# multiplier.net
KiCad netlist of a schematic drawn in Altium Designer
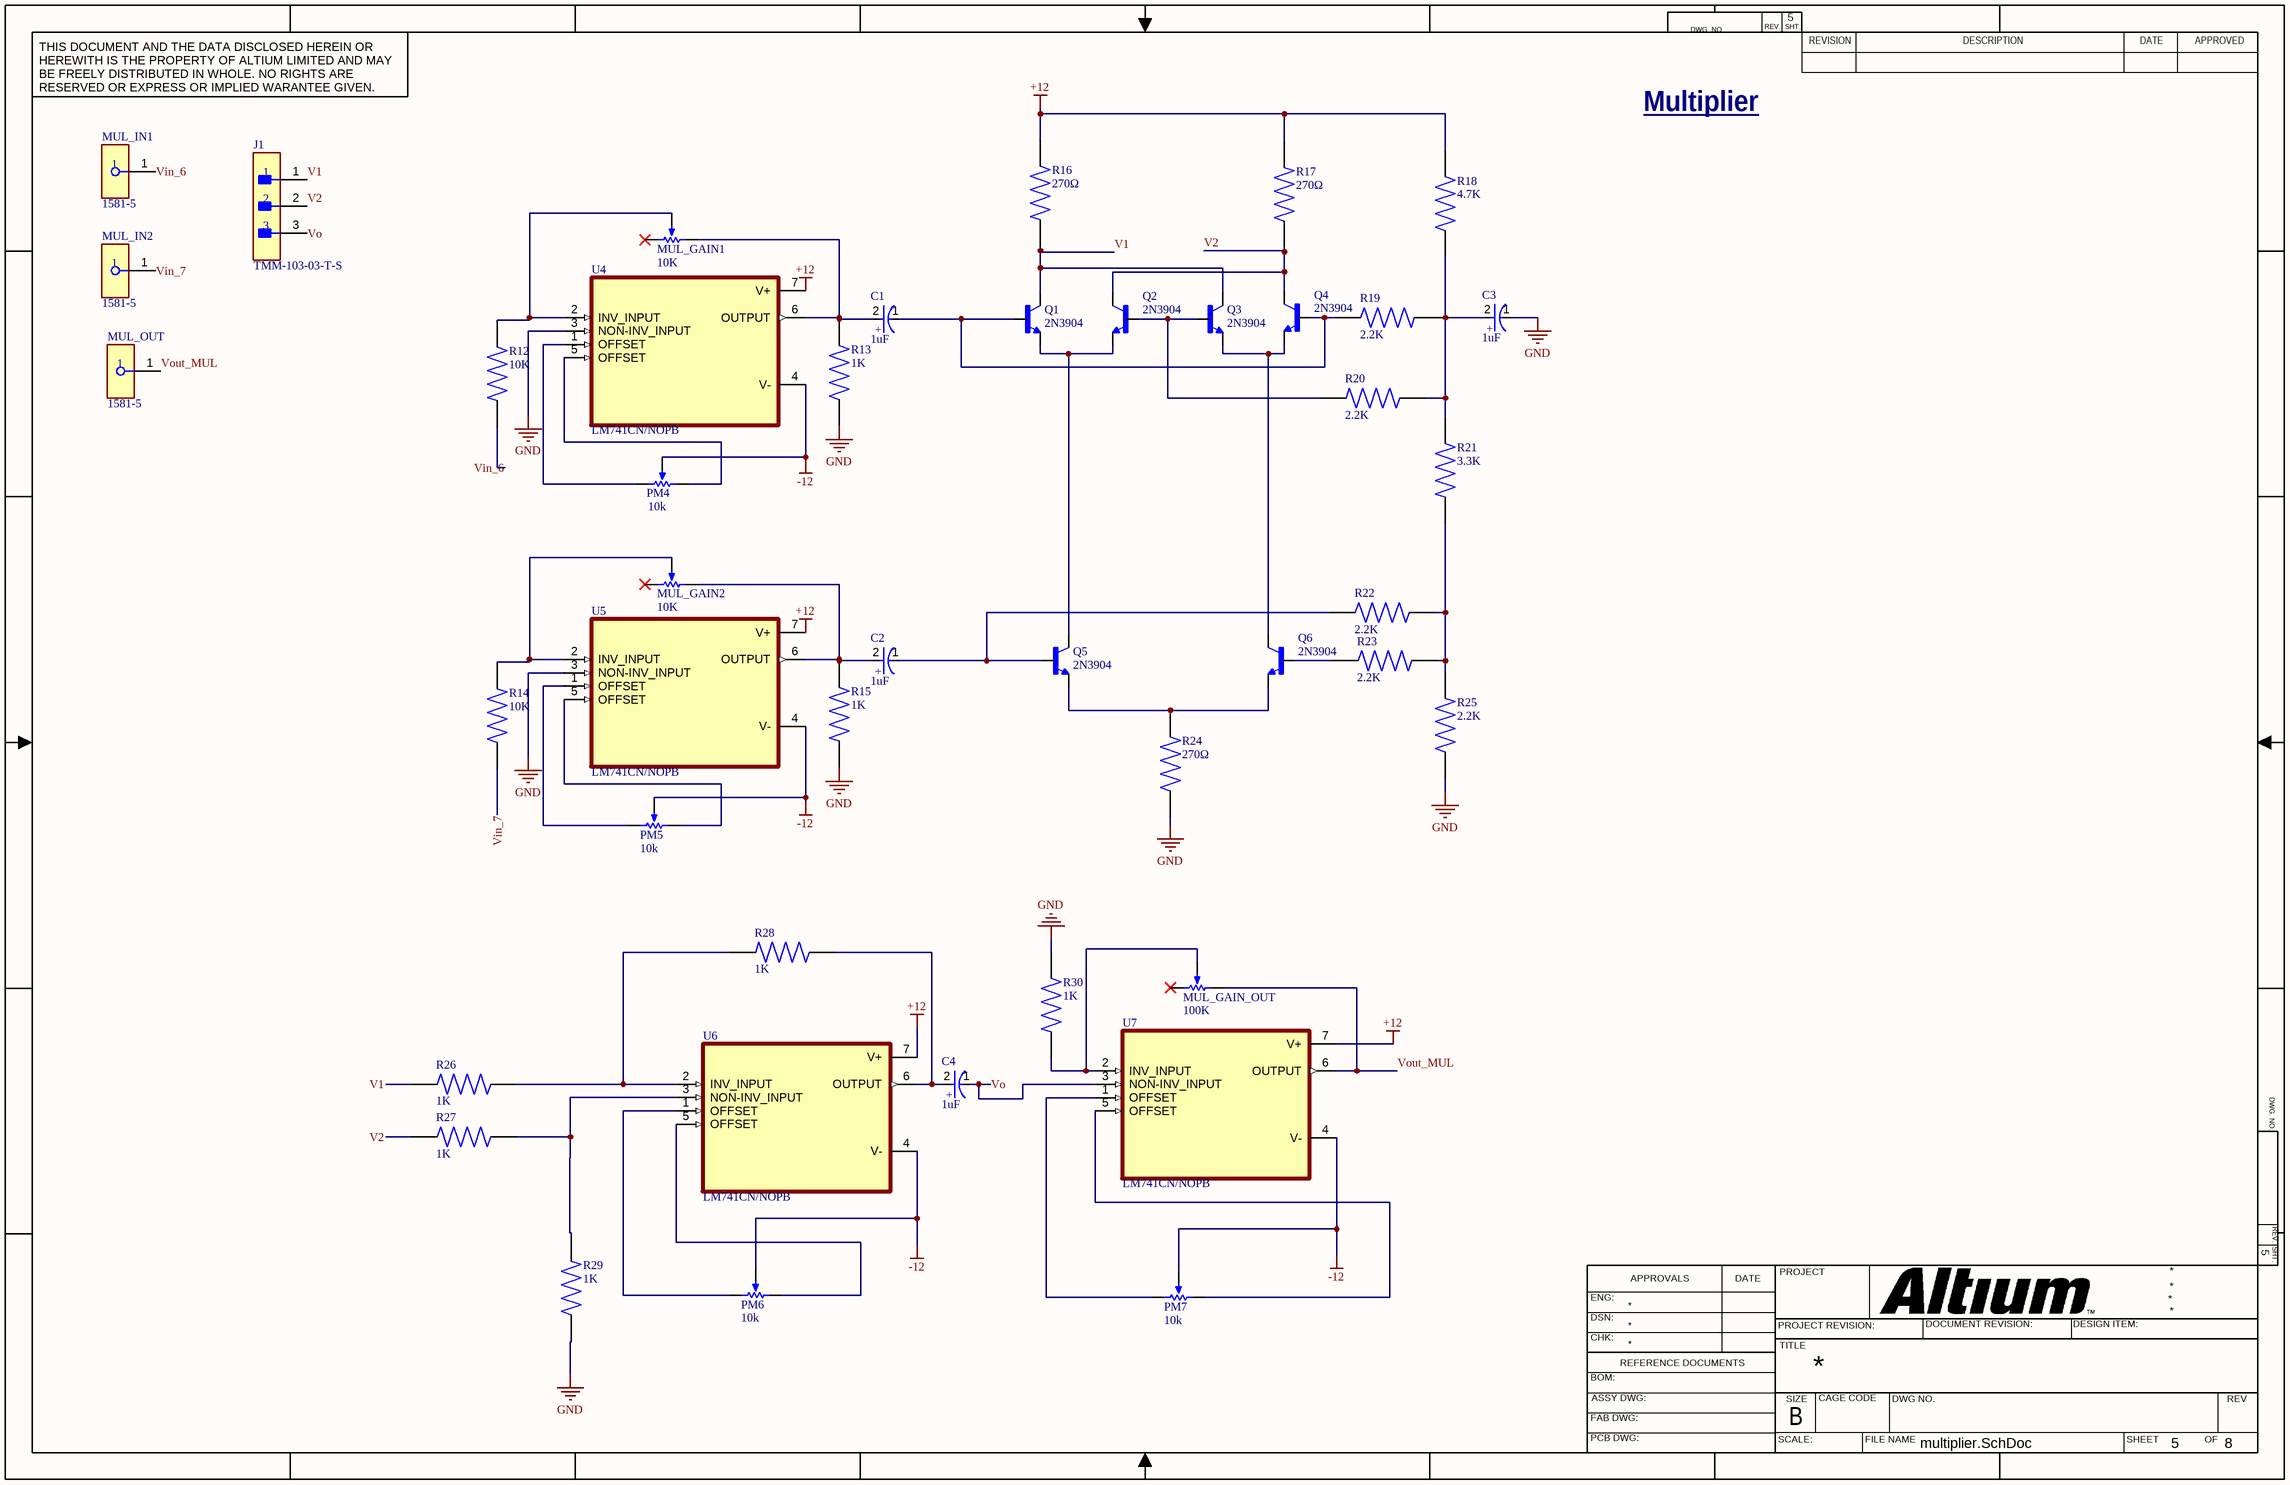
[diagram p0: multiplier.SchDoc]

(export (version "E")
  (design (tool "Eeschema 10.0.6"))
  (components
    (comp (ref "C1")
      (value "1uF")
      (footprint "FP-ECA-2CHG010I-MFG")
      (description "CAP ALUM 1UF 20% 160V RADIAL")
      (fields (field (name "TOLERANCE") "20%"))
      (libsource (lib "Altium Content Vault") (part "a00bbbee19879c290e62620ae7e47b1"))
    )
    (comp (ref "C2")
      (value "1uF")
      (footprint "FP-ECA-2CHG010I-MFG")
      (description "CAP ALUM 1UF 20% 160V RADIAL")
      (fields (field (name "TOLERANCE") "20%"))
      (libsource (lib "Altium Content Vault") (part "a00bbbee19879c290e62620ae7e47b1"))
    )
    (comp (ref "C3")
      (value "1uF")
      (footprint "FP-ECA-2CHG010I-MFG")
      (description "CAP ALUM 1UF 20% 160V RADIAL")
      (fields (field (name "TOLERANCE") "20%"))
      (libsource (lib "Altium Content Vault") (part "a00bbbee19879c290e62620ae7e47b1"))
    )
    (comp (ref "C4")
      (value "1uF")
      (footprint "FP-ECA-2CHG010I-MFG")
      (description "CAP ALUM 1UF 20% 160V RADIAL")
      (fields (field (name "TOLERANCE") "20%"))
      (libsource (lib "Altium Content Vault") (part "a00bbbee19879c290e62620ae7e47b1"))
    )
    (comp (ref "J1")
      (value "TMM-103-03-T-S")
      (footprint "FP-TMM-103-03-T-S-MFG")
      (description "CONN HEADER VERT 3POS 2MM")
      (libsource (lib "Altium Content Vault") (part "0d3f023dd272f625e17a2be33dea85f"))
    )
    (comp (ref "MUL_GAIN1")
      (value "10K")
      (footprint "BOUR-3852A-282-103AL-3_V")
      (description "Diameter Panel Control, 10 KOhm, +/- 10%, 2 W, -1 to 125 degC, 3-Pin THD, RoHS, Bulk")
      (fields (field (name "TOLERANCE") "±10%") (field (name "MANUFACTURER") "Bourns"))
      (libsource (lib "Altium Content Vault") (part "RES-POT-3"))
    )
    (comp (ref "MUL_GAIN2")
      (value "10K")
      (footprint "BOUR-3852A-282-103AL-3_V")
      (description "Diameter Panel Control, 10 KOhm, +/- 10%, 2 W, -1 to 125 degC, 3-Pin THD, RoHS, Bulk")
      (fields (field (name "TOLERANCE") "±10%") (field (name "MANUFACTURER") "Bourns"))
      (libsource (lib "Altium Content Vault") (part "RES-POT-3"))
    )
    (comp (ref "MUL_GAIN_OUT")
      (value "100K")
      (footprint "BOUR-3852A-282-103AL-3_V")
      (description "Diameter Panel Control, 10 KOhm, +/- 10%, 2 W, -1 to 125 degC, 3-Pin THD, RoHS, Bulk")
      (fields (field (name "TOLERANCE") "±10%") (field (name "MANUFACTURER") "Bourns"))
      (libsource (lib "Altium Content Vault") (part "RES-POT-3"))
    )
    (comp (ref "MUL_IN1")
      (value "1581-5")
      (footprint "FP-1581-5-MFG")
      (description "CONN BANANA JACK TURRET GREEN")
      (libsource (lib "Altium Content Vault") (part "c5c826e0c4b67fe3b42ef77f2d4decc"))
    )
    (comp (ref "MUL_IN2")
      (value "1581-5")
      (footprint "FP-1581-5-MFG")
      (description "CONN BANANA JACK TURRET GREEN")
      (libsource (lib "Altium Content Vault") (part "c5c826e0c4b67fe3b42ef77f2d4decc"))
    )
    (comp (ref "MUL_OUT")
      (value "1581-5")
      (footprint "FP-1581-5-MFG")
      (description "CONN BANANA JACK TURRET GREEN")
      (libsource (lib "Altium Content Vault") (part "c5c826e0c4b67fe3b42ef77f2d4decc"))
    )
    (comp (ref "PM4")
      (value "10k")
      (footprint "BOUR-3362P")
      (description "Square Trimpot(R) Trimming Potentiometer, 10 KOhm, 300 V, -55 to 125 degC, 3-Pin THD, RoHS, Tube")
      (fields (field (name "TOLERANCE") "1%"))
      (libsource (lib "Altium Content Vault") (part "RES-POT-3"))
    )
    (comp (ref "PM5")
      (value "10k")
      (footprint "BOUR-3362P")
      (description "Square Trimpot(R) Trimming Potentiometer, 10 KOhm, 300 V, -55 to 125 degC, 3-Pin THD, RoHS, Tube")
      (fields (field (name "TOLERANCE") "1%"))
      (libsource (lib "Altium Content Vault") (part "RES-POT-3"))
    )
    (comp (ref "PM6")
      (value "10k")
      (footprint "BOUR-3362P")
      (description "Square Trimpot(R) Trimming Potentiometer, 10 KOhm, 300 V, -55 to 125 degC, 3-Pin THD, RoHS, Tube")
      (fields (field (name "TOLERANCE") "1%"))
      (libsource (lib "Altium Content Vault") (part "RES-POT-3"))
    )
    (comp (ref "PM7")
      (value "10k")
      (footprint "BOUR-3362P")
      (description "Square Trimpot(R) Trimming Potentiometer, 10 KOhm, 300 V, -55 to 125 degC, 3-Pin THD, RoHS, Tube")
      (fields (field (name "TOLERANCE") "1%"))
      (libsource (lib "Altium Content Vault") (part "RES-POT-3"))
    )
    (comp (ref "Q1")
      (value "2N3904")
      (footprint "TO92254P460H750-3")
      (description "BJT, TO-92, 40V, 200mA, NPN, 0.625W, 150Â°C")
      (fields (field (name "MF") "Diotec Semiconductor"))
      (libsource (lib "") (part "2N3904_1"))
    )
    (comp (ref "Q2")
      (value "2N3904")
      (footprint "TO92254P460H750-3")
      (description "BJT, TO-92, 40V, 200mA, NPN, 0.625W, 150Â°C")
      (fields (field (name "MF") "Diotec Semiconductor"))
      (libsource (lib "2N3904") (part "2N3904"))
    )
    (comp (ref "Q3")
      (value "2N3904")
      (footprint "TO92254P460H750-3")
      (description "BJT, TO-92, 40V, 200mA, NPN, 0.625W, 150Â°C")
      (fields (field (name "MF") "Diotec Semiconductor"))
      (libsource (lib "") (part "2N3904_1"))
    )
    (comp (ref "Q4")
      (value "2N3904")
      (footprint "TO92254P460H750-3")
      (description "BJT, TO-92, 40V, 200mA, NPN, 0.625W, 150Â°C")
      (fields (field (name "MF") "Diotec Semiconductor"))
      (libsource (lib "2N3904") (part "2N3904"))
    )
    (comp (ref "Q5")
      (value "2N3904")
      (footprint "TO92254P460H750-3")
      (description "BJT, TO-92, 40V, 200mA, NPN, 0.625W, 150Â°C")
      (fields (field (name "MF") "Diotec Semiconductor"))
      (libsource (lib "") (part "2N3904_1"))
    )
    (comp (ref "Q6")
      (value "2N3904")
      (footprint "TO92254P460H750-3")
      (description "BJT, TO-92, 40V, 200mA, NPN, 0.625W, 150Â°C")
      (fields (field (name "MF") "Diotec Semiconductor"))
      (libsource (lib "2N3904") (part "2N3904"))
    )
    (comp (ref "R12")
      (value "10K")
      (footprint "RESAD1100W55L680D260")
      (description "1.07 kOhms Â±1% 0.25W, 1/4W Through Hole Resistor Axial - Metal Film")
      (fields (field (name "MF") "Yageo") (field (name "MP") "MFR-25FBF52-1K"))
      (libsource (lib "MFR-25FBF52-1K") (part "MFR-25FBF52-1K"))
    )
    (comp (ref "R13")
      (value "1K")
      (footprint "RESAD1100W55L680D260")
      (description "1.07 kOhms Â±1% 0.25W, 1/4W Through Hole Resistor Axial - Metal Film")
      (fields (field (name "MF") "Yageo") (field (name "MP") "MFR-25FBF52-1K"))
      (libsource (lib "MFR-25FBF52-1K") (part "MFR-25FBF52-1K"))
    )
    (comp (ref "R14")
      (value "10K")
      (footprint "RESAD1100W55L680D260")
      (description "1.07 kOhms Â±1% 0.25W, 1/4W Through Hole Resistor Axial - Metal Film")
      (fields (field (name "MF") "Yageo") (field (name "MP") "MFR-25FBF52-1K"))
      (libsource (lib "MFR-25FBF52-1K") (part "MFR-25FBF52-1K"))
    )
    (comp (ref "R15")
      (value "1K")
      (footprint "RESAD1100W55L680D260")
      (description "1.07 kOhms Â±1% 0.25W, 1/4W Through Hole Resistor Axial - Metal Film")
      (fields (field (name "MF") "Yageo") (field (name "MP") "MFR-25FBF52-1K"))
      (libsource (lib "MFR-25FBF52-1K") (part "MFR-25FBF52-1K"))
    )
    (comp (ref "R16")
      (value "270Ω")
      (footprint "RESAD1100W55L680D260")
      (description "1.07 kOhms Â±1% 0.25W, 1/4W Through Hole Resistor Axial - Metal Film")
      (fields (field (name "MF") "Yageo") (field (name "MP") "MFR-25FBF52-1K"))
      (libsource (lib "MFR-25FBF52-1K") (part "MFR-25FBF52-1K"))
    )
    (comp (ref "R17")
      (value "270Ω")
      (footprint "RESAD1100W55L680D260")
      (description "1.07 kOhms Â±1% 0.25W, 1/4W Through Hole Resistor Axial - Metal Film")
      (fields (field (name "MF") "Yageo") (field (name "MP") "MFR-25FBF52-1K"))
      (libsource (lib "MFR-25FBF52-1K") (part "MFR-25FBF52-1K"))
    )
    (comp (ref "R18")
      (value "4.7K")
      (footprint "RESAD1100W55L680D260")
      (description "1.07 kOhms Â±1% 0.25W, 1/4W Through Hole Resistor Axial - Metal Film")
      (fields (field (name "MF") "Yageo") (field (name "MP") "MFR-25FBF52-1K"))
      (libsource (lib "MFR-25FBF52-1K") (part "MFR-25FBF52-1K"))
    )
    (comp (ref "R19")
      (value "2.2K")
      (footprint "RESAD1100W55L680D260")
      (description "1.07 kOhms Â±1% 0.25W, 1/4W Through Hole Resistor Axial - Metal Film")
      (fields (field (name "MF") "Yageo") (field (name "MP") "MFR-25FBF52-1K"))
      (libsource (lib "MFR-25FBF52-1K") (part "MFR-25FBF52-1K"))
    )
    (comp (ref "R20")
      (value "2.2K")
      (footprint "RESAD1100W55L680D260")
      (description "1.07 kOhms Â±1% 0.25W, 1/4W Through Hole Resistor Axial - Metal Film")
      (fields (field (name "MF") "Yageo") (field (name "MP") "MFR-25FBF52-1K"))
      (libsource (lib "MFR-25FBF52-1K") (part "MFR-25FBF52-1K"))
    )
    (comp (ref "R21")
      (value "3.3K")
      (footprint "RESAD1100W55L680D260")
      (description "1.07 kOhms Â±1% 0.25W, 1/4W Through Hole Resistor Axial - Metal Film")
      (fields (field (name "MF") "Yageo") (field (name "MP") "MFR-25FBF52-1K"))
      (libsource (lib "MFR-25FBF52-1K") (part "MFR-25FBF52-1K"))
    )
    (comp (ref "R22")
      (value "2.2K")
      (footprint "RESAD1100W55L680D260")
      (description "1.07 kOhms Â±1% 0.25W, 1/4W Through Hole Resistor Axial - Metal Film")
      (fields (field (name "MF") "Yageo") (field (name "MP") "MFR-25FBF52-1K"))
      (libsource (lib "MFR-25FBF52-1K") (part "MFR-25FBF52-1K"))
    )
    (comp (ref "R23")
      (value "2.2K")
      (footprint "RESAD1100W55L680D260")
      (description "1.07 kOhms Â±1% 0.25W, 1/4W Through Hole Resistor Axial - Metal Film")
      (fields (field (name "MF") "Yageo") (field (name "MP") "MFR-25FBF52-1K"))
      (libsource (lib "MFR-25FBF52-1K") (part "MFR-25FBF52-1K"))
    )
    (comp (ref "R24")
      (value "270Ω")
      (footprint "RESAD1100W55L680D260")
      (description "1.07 kOhms Â±1% 0.25W, 1/4W Through Hole Resistor Axial - Metal Film")
      (fields (field (name "MF") "Yageo") (field (name "MP") "MFR-25FBF52-1K"))
      (libsource (lib "MFR-25FBF52-1K") (part "MFR-25FBF52-1K"))
    )
    (comp (ref "R25")
      (value "2.2K")
      (footprint "RESAD1100W55L680D260")
      (description "1.07 kOhms Â±1% 0.25W, 1/4W Through Hole Resistor Axial - Metal Film")
      (fields (field (name "MF") "Yageo") (field (name "MP") "MFR-25FBF52-1K"))
      (libsource (lib "MFR-25FBF52-1K") (part "MFR-25FBF52-1K"))
    )
    (comp (ref "R26")
      (value "1K")
      (footprint "RESAD1100W55L680D260")
      (description "1.07 kOhms Â±1% 0.25W, 1/4W Through Hole Resistor Axial - Metal Film")
      (fields (field (name "MF") "Yageo") (field (name "MP") "MFR-25FBF52-1K"))
      (libsource (lib "MFR-25FBF52-1K") (part "MFR-25FBF52-1K"))
    )
    (comp (ref "R27")
      (value "1K")
      (footprint "RESAD1100W55L680D260")
      (description "1.07 kOhms Â±1% 0.25W, 1/4W Through Hole Resistor Axial - Metal Film")
      (fields (field (name "MF") "Yageo") (field (name "MP") "MFR-25FBF52-1K"))
      (libsource (lib "MFR-25FBF52-1K") (part "MFR-25FBF52-1K"))
    )
    (comp (ref "R28")
      (value "1K")
      (footprint "RESAD1100W55L680D260")
      (description "1.07 kOhms Â±1% 0.25W, 1/4W Through Hole Resistor Axial - Metal Film")
      (fields (field (name "MF") "Yageo") (field (name "MP") "MFR-25FBF52-1K"))
      (libsource (lib "MFR-25FBF52-1K") (part "MFR-25FBF52-1K"))
    )
    (comp (ref "R29")
      (value "1K")
      (footprint "RESAD1100W55L680D260")
      (description "1.07 kOhms Â±1% 0.25W, 1/4W Through Hole Resistor Axial - Metal Film")
      (fields (field (name "MF") "Yageo") (field (name "MP") "MFR-25FBF52-1K"))
      (libsource (lib "MFR-25FBF52-1K") (part "MFR-25FBF52-1K"))
    )
    (comp (ref "R30")
      (value "1K")
      (footprint "RESAD1100W55L680D260")
      (description "1.07 kOhms Â±1% 0.25W, 1/4W Through Hole Resistor Axial - Metal Film")
      (fields (field (name "MF") "Yageo") (field (name "MP") "MFR-25FBF52-1K"))
      (libsource (lib "MFR-25FBF52-1K") (part "MFR-25FBF52-1K"))
    )
    (comp (ref "U4")
      (value "LM741CN/NOPB")
      (footprint "DIP794W45P254L959H508Q8")
      (description "Single, 44-V, 1-MHz operational amplifier")
      (fields (field (name "MF") "Texas Instruments"))
      (libsource (lib "LM741CN_NOPB (1)") (part "LM741CN/NOPB"))
    )
    (comp (ref "U5")
      (value "LM741CN/NOPB")
      (footprint "DIP794W45P254L959H508Q8")
      (description "Single, 44-V, 1-MHz operational amplifier")
      (fields (field (name "MF") "Texas Instruments"))
      (libsource (lib "LM741CN_NOPB (1)") (part "LM741CN/NOPB"))
    )
    (comp (ref "U6")
      (value "LM741CN/NOPB")
      (footprint "DIP794W45P254L959H508Q8")
      (description "Single, 44-V, 1-MHz operational amplifier")
      (fields (field (name "MF") "Texas Instruments"))
      (libsource (lib "LM741CN_NOPB (1)") (part "LM741CN/NOPB"))
    )
    (comp (ref "U7")
      (value "LM741CN/NOPB")
      (footprint "DIP794W45P254L959H508Q8")
      (description "Single, 44-V, 1-MHz operational amplifier")
      (fields (field (name "MF") "Texas Instruments"))
      (libsource (lib "LM741CN_NOPB (1)") (part "LM741CN/NOPB"))
    )
  )
  (nets
    (net (code "1") (name "+12") (class "Default")
      (node (ref "R16") (pin "2") (pinfunction "2_2") (pintype "passive"))
      (node (ref "R17") (pin "2") (pinfunction "2_2") (pintype "passive"))
      (node (ref "R18") (pin "2") (pinfunction "2_2") (pintype "passive"))
      (node (ref "U4") (pin "7") (pinfunction "V+_7") (pintype "power_in"))
      (node (ref "U5") (pin "7") (pinfunction "V+_7") (pintype "power_in"))
      (node (ref "U6") (pin "7") (pinfunction "V+_7") (pintype "power_in"))
      (node (ref "U7") (pin "7") (pinfunction "V+_7") (pintype "power_in"))
    )
    (net (code "2") (name "-12") (class "Default")
      (node (ref "PM4") (pin "2") (pinfunction "S_2") (pintype "passive"))
      (node (ref "PM5") (pin "2") (pinfunction "S_2") (pintype "passive"))
      (node (ref "PM6") (pin "2") (pinfunction "S_2") (pintype "passive"))
      (node (ref "PM7") (pin "2") (pinfunction "S_2") (pintype "passive"))
      (node (ref "U4") (pin "4") (pinfunction "V-_4") (pintype "power_in"))
      (node (ref "U5") (pin "4") (pinfunction "V-_4") (pintype "power_in"))
      (node (ref "U6") (pin "4") (pinfunction "V-_4") (pintype "power_in"))
      (node (ref "U7") (pin "4") (pinfunction "V-_4") (pintype "power_in"))
    )
    (net (code "3") (name "/V1") (class "Default")
      (node (ref "J1") (pin "1") (pinfunction "1_1") (pintype "passive"))
      (node (ref "Q1") (pin "3") (pinfunction "C_3") (pintype "passive"))
      (node (ref "Q3") (pin "3") (pinfunction "C_3") (pintype "passive"))
      (node (ref "R16") (pin "1") (pinfunction "1_1") (pintype "passive"))
      (node (ref "R26") (pin "1") (pinfunction "1_1") (pintype "passive"))
    )
    (net (code "4") (name "/V2") (class "Default")
      (node (ref "J1") (pin "2") (pinfunction "2_2") (pintype "passive"))
      (node (ref "Q2") (pin "3") (pinfunction "C_3") (pintype "passive"))
      (node (ref "Q4") (pin "3") (pinfunction "C_3") (pintype "passive"))
      (node (ref "R17") (pin "1") (pinfunction "1_1") (pintype "passive"))
      (node (ref "R27") (pin "1") (pinfunction "1_1") (pintype "passive"))
    )
    (net (code "5") (name "/Vin_6") (class "Default")
      (node (ref "MUL_IN1") (pin "1") (pinfunction "1_1") (pintype "passive"))
      (node (ref "R12") (pin "1") (pinfunction "1_1") (pintype "passive"))
    )
    (net (code "6") (name "/Vin_7") (class "Default")
      (node (ref "MUL_IN2") (pin "1") (pinfunction "1_1") (pintype "passive"))
      (node (ref "R14") (pin "1") (pinfunction "1_1") (pintype "passive"))
    )
    (net (code "7") (name "/Vo") (class "Default")
      (node (ref "C4") (pin "1") (pinfunction "C_1") (pintype "passive"))
      (node (ref "J1") (pin "3") (pinfunction "3_3") (pintype "passive"))
      (node (ref "U7") (pin "3") (pinfunction "NON-INV_INPUT_3") (pintype "input"))
    )
    (net (code "8") (name "/Vout_MUL") (class "Default")
      (node (ref "MUL_GAIN_OUT") (pin "1") (pinfunction "CCW_1") (pintype "passive"))
      (node (ref "MUL_OUT") (pin "1") (pinfunction "1_1") (pintype "passive"))
      (node (ref "U7") (pin "6") (pinfunction "OUTPUT_6") (pintype "output"))
    )
    (net (code "9") (name "GND") (class "Default")
      (node (ref "C3") (pin "1") (pinfunction "C_1") (pintype "passive"))
      (node (ref "R13") (pin "1") (pinfunction "1_1") (pintype "passive"))
      (node (ref "R15") (pin "1") (pinfunction "1_1") (pintype "passive"))
      (node (ref "R24") (pin "1") (pinfunction "1_1") (pintype "passive"))
      (node (ref "R25") (pin "1") (pinfunction "1_1") (pintype "passive"))
      (node (ref "R29") (pin "1") (pinfunction "1_1") (pintype "passive"))
      (node (ref "R30") (pin "1") (pinfunction "1_1") (pintype "passive"))
      (node (ref "U4") (pin "3") (pinfunction "NON-INV_INPUT_3") (pintype "input"))
      (node (ref "U5") (pin "3") (pinfunction "NON-INV_INPUT_3") (pintype "input"))
    )
    (net (code "10") (name "Net-(C1-A)") (class "Default")
      (node (ref "C1") (pin "2") (pinfunction "A_2") (pintype "passive"))
      (node (ref "MUL_GAIN1") (pin "1") (pinfunction "CCW_1") (pintype "passive"))
      (node (ref "R13") (pin "2") (pinfunction "2_2") (pintype "passive"))
      (node (ref "U4") (pin "6") (pinfunction "OUTPUT_6") (pintype "output"))
    )
    (net (code "11") (name "Net-(C1-C)") (class "Default")
      (node (ref "C1") (pin "1") (pinfunction "C_1") (pintype "passive"))
      (node (ref "Q1") (pin "2") (pinfunction "B_2") (pintype "passive"))
      (node (ref "Q4") (pin "2") (pinfunction "B_2") (pintype "passive"))
      (node (ref "R19") (pin "1") (pinfunction "1_1") (pintype "passive"))
    )
    (net (code "12") (name "Net-(C2-A)") (class "Default")
      (node (ref "C2") (pin "2") (pinfunction "A_2") (pintype "passive"))
      (node (ref "MUL_GAIN2") (pin "1") (pinfunction "CCW_1") (pintype "passive"))
      (node (ref "R15") (pin "2") (pinfunction "2_2") (pintype "passive"))
      (node (ref "U5") (pin "6") (pinfunction "OUTPUT_6") (pintype "output"))
    )
    (net (code "13") (name "Net-(C2-C)") (class "Default")
      (node (ref "C2") (pin "1") (pinfunction "C_1") (pintype "passive"))
      (node (ref "Q5") (pin "2") (pinfunction "B_2") (pintype "passive"))
      (node (ref "R22") (pin "1") (pinfunction "1_1") (pintype "passive"))
    )
    (net (code "14") (name "Net-(C3-A)") (class "Default")
      (node (ref "C3") (pin "2") (pinfunction "A_2") (pintype "passive"))
      (node (ref "R18") (pin "1") (pinfunction "1_1") (pintype "passive"))
      (node (ref "R19") (pin "2") (pinfunction "2_2") (pintype "passive"))
      (node (ref "R20") (pin "2") (pinfunction "2_2") (pintype "passive"))
      (node (ref "R21") (pin "2") (pinfunction "2_2") (pintype "passive"))
    )
    (net (code "15") (name "Net-(C4-A)") (class "Default")
      (node (ref "C4") (pin "2") (pinfunction "A_2") (pintype "passive"))
      (node (ref "R28") (pin "2") (pinfunction "2_2") (pintype "passive"))
      (node (ref "U6") (pin "6") (pinfunction "OUTPUT_6") (pintype "output"))
    )
    (net (code "16") (name "Net-(MUL_GAIN1-S)") (class "Default")
      (node (ref "MUL_GAIN1") (pin "2") (pinfunction "S_2") (pintype "passive"))
      (node (ref "R12") (pin "2") (pinfunction "2_2") (pintype "passive"))
      (node (ref "U4") (pin "2") (pinfunction "INV_INPUT_2") (pintype "input"))
    )
    (net (code "17") (name "Net-(MUL_GAIN2-S)") (class "Default")
      (node (ref "MUL_GAIN2") (pin "2") (pinfunction "S_2") (pintype "passive"))
      (node (ref "R14") (pin "2") (pinfunction "2_2") (pintype "passive"))
      (node (ref "U5") (pin "2") (pinfunction "INV_INPUT_2") (pintype "input"))
    )
    (net (code "18") (name "Net-(MUL_GAIN_OUT-S)") (class "Default")
      (node (ref "MUL_GAIN_OUT") (pin "2") (pinfunction "S_2") (pintype "passive"))
      (node (ref "R30") (pin "2") (pinfunction "2_2") (pintype "passive"))
      (node (ref "U7") (pin "2") (pinfunction "INV_INPUT_2") (pintype "input"))
    )
    (net (code "19") (name "Net-(PM4-CCW)") (class "Default")
      (node (ref "PM4") (pin "1") (pinfunction "CCW_1") (pintype "passive"))
      (node (ref "U4") (pin "5") (pinfunction "OFFSET_5") (pintype "input"))
    )
    (net (code "20") (name "Net-(PM4-CW)") (class "Default")
      (node (ref "PM4") (pin "3") (pinfunction "CW_3") (pintype "passive"))
      (node (ref "U4") (pin "1") (pinfunction "OFFSET_1") (pintype "input"))
    )
    (net (code "21") (name "Net-(PM5-CCW)") (class "Default")
      (node (ref "PM5") (pin "1") (pinfunction "CCW_1") (pintype "passive"))
      (node (ref "U5") (pin "5") (pinfunction "OFFSET_5") (pintype "input"))
    )
    (net (code "22") (name "Net-(PM5-CW)") (class "Default")
      (node (ref "PM5") (pin "3") (pinfunction "CW_3") (pintype "passive"))
      (node (ref "U5") (pin "1") (pinfunction "OFFSET_1") (pintype "input"))
    )
    (net (code "23") (name "Net-(PM6-CCW)") (class "Default")
      (node (ref "PM6") (pin "1") (pinfunction "CCW_1") (pintype "passive"))
      (node (ref "U6") (pin "5") (pinfunction "OFFSET_5") (pintype "input"))
    )
    (net (code "24") (name "Net-(PM6-CW)") (class "Default")
      (node (ref "PM6") (pin "3") (pinfunction "CW_3") (pintype "passive"))
      (node (ref "U6") (pin "1") (pinfunction "OFFSET_1") (pintype "input"))
    )
    (net (code "25") (name "Net-(PM7-CCW)") (class "Default")
      (node (ref "PM7") (pin "1") (pinfunction "CCW_1") (pintype "passive"))
      (node (ref "U7") (pin "5") (pinfunction "OFFSET_5") (pintype "input"))
    )
    (net (code "26") (name "Net-(PM7-CW)") (class "Default")
      (node (ref "PM7") (pin "3") (pinfunction "CW_3") (pintype "passive"))
      (node (ref "U7") (pin "1") (pinfunction "OFFSET_1") (pintype "input"))
    )
    (net (code "27") (name "Net-(Q1-E)") (class "Default")
      (node (ref "Q1") (pin "1") (pinfunction "E_1") (pintype "passive"))
      (node (ref "Q2") (pin "1") (pinfunction "E_1") (pintype "passive"))
      (node (ref "Q5") (pin "3") (pinfunction "C_3") (pintype "passive"))
    )
    (net (code "28") (name "Net-(Q2-B)") (class "Default")
      (node (ref "Q2") (pin "2") (pinfunction "B_2") (pintype "passive"))
      (node (ref "Q3") (pin "2") (pinfunction "B_2") (pintype "passive"))
      (node (ref "R20") (pin "1") (pinfunction "1_1") (pintype "passive"))
    )
    (net (code "29") (name "Net-(Q3-E)") (class "Default")
      (node (ref "Q3") (pin "1") (pinfunction "E_1") (pintype "passive"))
      (node (ref "Q4") (pin "1") (pinfunction "E_1") (pintype "passive"))
      (node (ref "Q6") (pin "3") (pinfunction "C_3") (pintype "passive"))
    )
    (net (code "30") (name "Net-(Q5-E)") (class "Default")
      (node (ref "Q5") (pin "1") (pinfunction "E_1") (pintype "passive"))
      (node (ref "Q6") (pin "1") (pinfunction "E_1") (pintype "passive"))
      (node (ref "R24") (pin "2") (pinfunction "2_2") (pintype "passive"))
    )
    (net (code "31") (name "Net-(Q6-B)") (class "Default")
      (node (ref "Q6") (pin "2") (pinfunction "B_2") (pintype "passive"))
      (node (ref "R23") (pin "1") (pinfunction "1_1") (pintype "passive"))
    )
    (net (code "32") (name "Net-(R21-Pad1)") (class "Default")
      (node (ref "R21") (pin "1") (pinfunction "1_1") (pintype "passive"))
      (node (ref "R22") (pin "2") (pinfunction "2_2") (pintype "passive"))
      (node (ref "R23") (pin "2") (pinfunction "2_2") (pintype "passive"))
      (node (ref "R25") (pin "2") (pinfunction "2_2") (pintype "passive"))
    )
    (net (code "33") (name "Net-(U6-INV_INPUT)") (class "Default")
      (node (ref "R26") (pin "2") (pinfunction "2_2") (pintype "passive"))
      (node (ref "R28") (pin "1") (pinfunction "1_1") (pintype "passive"))
      (node (ref "U6") (pin "2") (pinfunction "INV_INPUT_2") (pintype "input"))
    )
    (net (code "34") (name "Net-(U6-NON-INV_INPUT)") (class "Default")
      (node (ref "R27") (pin "2") (pinfunction "2_2") (pintype "passive"))
      (node (ref "R29") (pin "2") (pinfunction "2_2") (pintype "passive"))
      (node (ref "U6") (pin "3") (pinfunction "NON-INV_INPUT_3") (pintype "input"))
    )
    (net (code "35") (name "unconnected-(MUL_GAIN1-CW-Pad3)") (class "Default")
      (node (ref "MUL_GAIN1") (pin "3") (pinfunction "CW_3") (pintype "passive+no_connect"))
    )
    (net (code "36") (name "unconnected-(MUL_GAIN2-CW-Pad3)") (class "Default")
      (node (ref "MUL_GAIN2") (pin "3") (pinfunction "CW_3") (pintype "passive+no_connect"))
    )
    (net (code "37") (name "unconnected-(MUL_GAIN_OUT-CW-Pad3)") (class "Default")
      (node (ref "MUL_GAIN_OUT") (pin "3") (pinfunction "CW_3") (pintype "passive+no_connect"))
    )
  )
)
